# SCH_New-Project_2024-05-19.net
KiCad netlist of a schematic drawn in EasyEDA
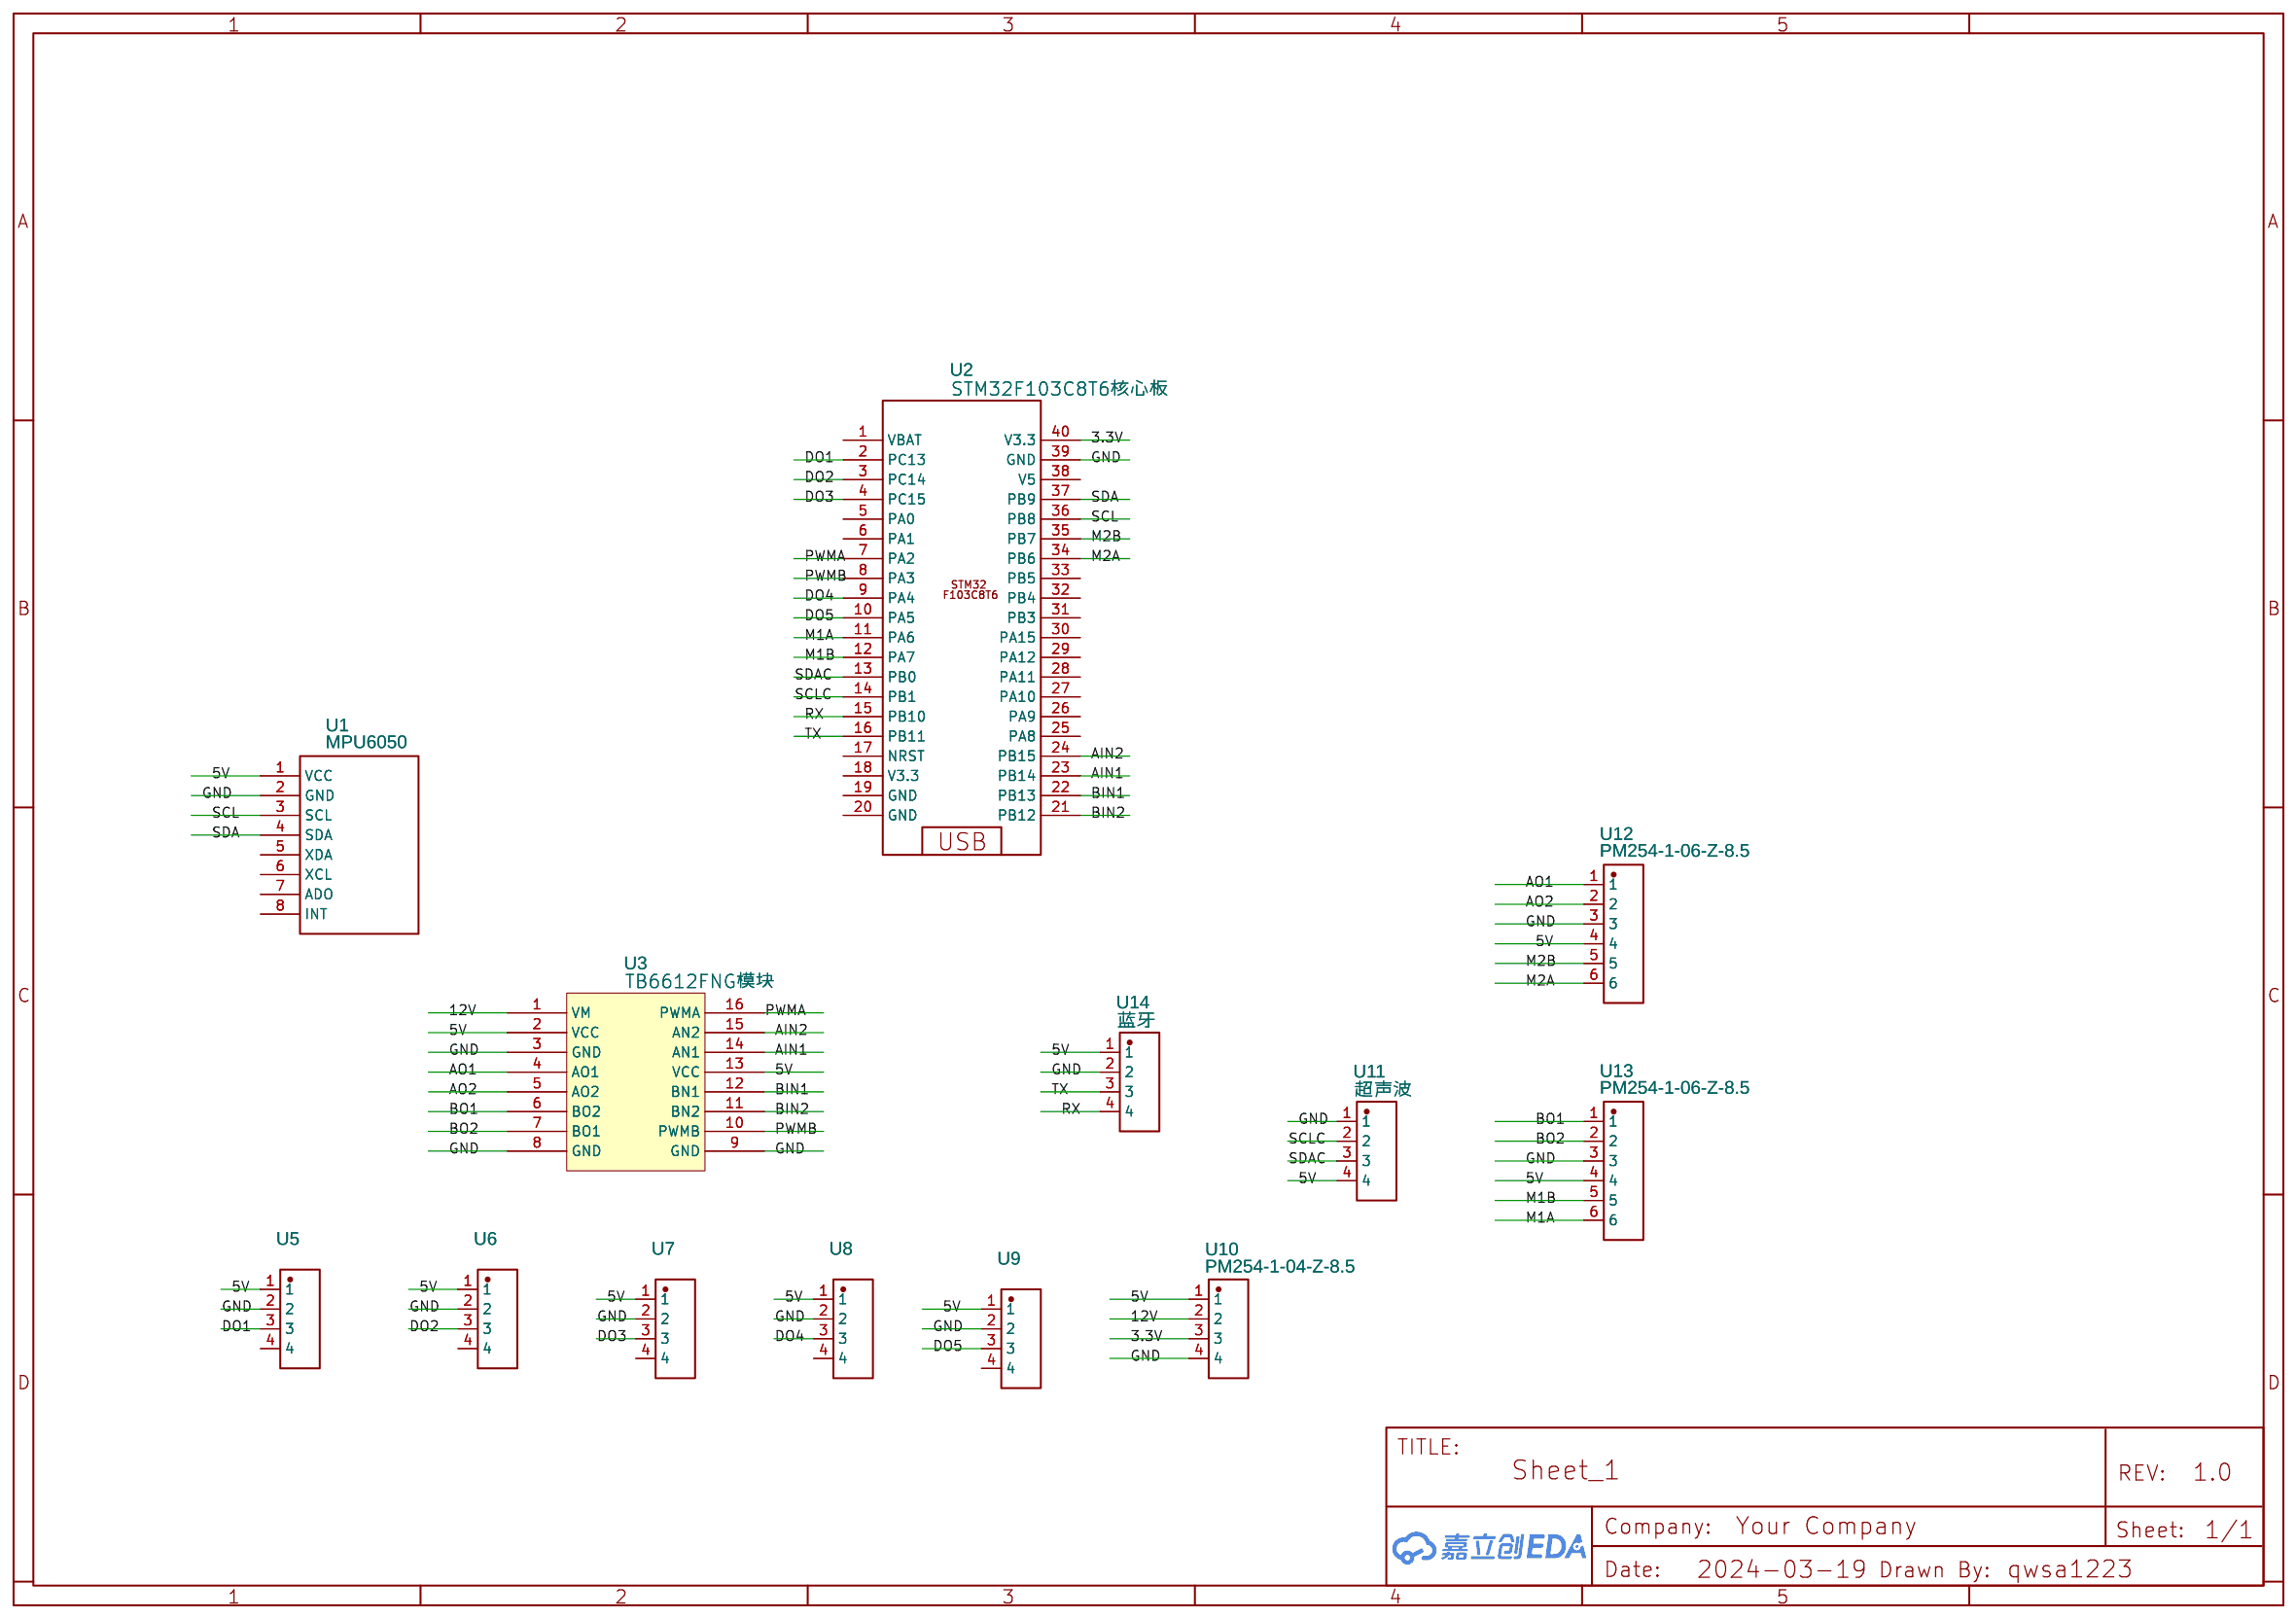
[diagram p0: schematic sheet]

(export (version "E")
  (design (tool "Eeschema 10.0.6"))
  (components
    (comp (ref "U1") (value "MPU6050") (libsource (lib "") (part "MPU6050")))
    (comp (ref "U2") (value "STM32F103C8T6核心板") (libsource (lib "") (part "STM32F103C8T6核心板")))
    (comp (ref "U3") (value "TB6612FNG模块") (libsource (lib "") (part "TB6612FNG模块")))
    (comp (ref "U5")
      (value "PM254-1-04-W-8.5")
      (fields (field (name "Manufacturer") "HCTL(华灿天禄)"))
      (libsource (lib "") (part "PM254-1-04-W-8.5"))
    )
    (comp (ref "U6")
      (value "PM254-1-04-W-8.5")
      (fields (field (name "Manufacturer") "HCTL(华灿天禄)"))
      (libsource (lib "") (part "PM254-1-04-W-8.5"))
    )
    (comp (ref "U7")
      (value "PM254-1-04-W-8.5")
      (fields (field (name "Manufacturer") "HCTL(华灿天禄)"))
      (libsource (lib "") (part "PM254-1-04-W-8.5"))
    )
    (comp (ref "U8")
      (value "PM254-1-04-W-8.5")
      (fields (field (name "Manufacturer") "HCTL(华灿天禄)"))
      (libsource (lib "") (part "PM254-1-04-W-8.5"))
    )
    (comp (ref "U9")
      (value "PM254-1-04-W-8.5")
      (fields (field (name "Manufacturer") "HCTL(华灿天禄)"))
      (libsource (lib "") (part "PM254-1-04-W-8.5"))
    )
    (comp (ref "U10")
      (value "PM254-1-04-Z-8.5")
      (fields (field (name "Manufacturer") "HCTL(华灿天禄)"))
      (libsource (lib "") (part "PM254-1-04-Z-8.5"))
    )
    (comp (ref "U11")
      (value "超声波")
      (fields
        (field (name "Manufacturer Part") "PM254-1-04-Z-8.5")
        (field (name "Manufacturer") "HCTL(华灿天禄)")
      )
      (libsource (lib "") (part "PM254-1-04-Z-8.5"))
    )
    (comp (ref "U12")
      (value "PM254-1-06-Z-8.5")
      (fields (field (name "Manufacturer") "HCTL(华灿天禄)"))
      (libsource (lib "") (part "PM254-1-06-Z-8.5"))
    )
    (comp (ref "U13")
      (value "PM254-1-06-Z-8.5")
      (fields (field (name "Manufacturer") "HCTL(华灿天禄)"))
      (libsource (lib "") (part "PM254-1-06-Z-8.5"))
    )
    (comp (ref "U14")
      (value "蓝牙")
      (fields
        (field (name "Manufacturer Part") "PM254-1-04-Z-8.5")
        (field (name "Manufacturer") "HCTL(华灿天禄)")
      )
      (libsource (lib "") (part "PM254-1-04-Z-8.5"))
    )
  )
  (nets
    (net (code "1") (name "/3.3V") (class "Default")
      (node (ref "U10") (pin "3") (pinfunction "3_3") (pintype "unspecified"))
      (node (ref "U2") (pin "40") (pinfunction "V3.3_40") (pintype "passive"))
    )
    (net (code "2") (name "/5V") (class "Default")
      (node (ref "U1") (pin "1") (pinfunction "VCC_1") (pintype "unspecified"))
      (node (ref "U10") (pin "1") (pinfunction "1_1") (pintype "unspecified"))
      (node (ref "U11") (pin "4") (pinfunction "4_4") (pintype "unspecified"))
      (node (ref "U12") (pin "4") (pinfunction "4_4") (pintype "unspecified"))
      (node (ref "U13") (pin "4") (pinfunction "4_4") (pintype "unspecified"))
      (node (ref "U14") (pin "1") (pinfunction "1_1") (pintype "unspecified"))
      (node (ref "U3") (pin "13") (pinfunction "VCC_13") (pintype "unspecified"))
      (node (ref "U3") (pin "2") (pinfunction "VCC_2") (pintype "unspecified"))
      (node (ref "U5") (pin "1") (pinfunction "1_1") (pintype "unspecified"))
      (node (ref "U6") (pin "1") (pinfunction "1_1") (pintype "unspecified"))
      (node (ref "U7") (pin "1") (pinfunction "1_1") (pintype "unspecified"))
      (node (ref "U8") (pin "1") (pinfunction "1_1") (pintype "unspecified"))
      (node (ref "U9") (pin "1") (pinfunction "1_1") (pintype "unspecified"))
    )
    (net (code "3") (name "/12V") (class "Default")
      (node (ref "U10") (pin "2") (pinfunction "2_2") (pintype "unspecified"))
      (node (ref "U3") (pin "1") (pinfunction "VM_1") (pintype "unspecified"))
    )
    (net (code "4") (name "/AIN1") (class "Default")
      (node (ref "U2") (pin "23") (pinfunction "PB14_23") (pintype "bidirectional"))
      (node (ref "U3") (pin "14") (pinfunction "AN1_14") (pintype "unspecified"))
    )
    (net (code "5") (name "/AIN2") (class "Default")
      (node (ref "U2") (pin "24") (pinfunction "PB15_24") (pintype "bidirectional"))
      (node (ref "U3") (pin "15") (pinfunction "AN2_15") (pintype "unspecified"))
    )
    (net (code "6") (name "/AO1") (class "Default")
      (node (ref "U12") (pin "1") (pinfunction "1_1") (pintype "unspecified"))
      (node (ref "U3") (pin "4") (pinfunction "AO1_4") (pintype "unspecified"))
    )
    (net (code "7") (name "/AO2") (class "Default")
      (node (ref "U12") (pin "2") (pinfunction "2_2") (pintype "unspecified"))
      (node (ref "U3") (pin "5") (pinfunction "AO2_5") (pintype "unspecified"))
    )
    (net (code "8") (name "/BIN1") (class "Default")
      (node (ref "U2") (pin "22") (pinfunction "PB13_22") (pintype "bidirectional"))
      (node (ref "U3") (pin "12") (pinfunction "BN1_12") (pintype "unspecified"))
    )
    (net (code "9") (name "/BIN2") (class "Default")
      (node (ref "U2") (pin "21") (pinfunction "PB12_21") (pintype "bidirectional"))
      (node (ref "U3") (pin "11") (pinfunction "BN2_11") (pintype "unspecified"))
    )
    (net (code "10") (name "/BO1") (class "Default")
      (node (ref "U13") (pin "1") (pinfunction "1_1") (pintype "unspecified"))
      (node (ref "U3") (pin "6") (pinfunction "BO2_6") (pintype "unspecified"))
    )
    (net (code "11") (name "/BO2") (class "Default")
      (node (ref "U13") (pin "2") (pinfunction "2_2") (pintype "unspecified"))
      (node (ref "U3") (pin "7") (pinfunction "BO1_7") (pintype "unspecified"))
    )
    (net (code "12") (name "/DO1") (class "Default")
      (node (ref "U2") (pin "2") (pinfunction "PC13_2") (pintype "bidirectional"))
      (node (ref "U5") (pin "3") (pinfunction "3_3") (pintype "unspecified"))
    )
    (net (code "13") (name "/DO2") (class "Default")
      (node (ref "U2") (pin "3") (pinfunction "PC14_3") (pintype "bidirectional"))
      (node (ref "U6") (pin "3") (pinfunction "3_3") (pintype "unspecified"))
    )
    (net (code "14") (name "/DO3") (class "Default")
      (node (ref "U2") (pin "4") (pinfunction "PC15_4") (pintype "bidirectional"))
      (node (ref "U7") (pin "3") (pinfunction "3_3") (pintype "unspecified"))
    )
    (net (code "15") (name "/DO4") (class "Default")
      (node (ref "U2") (pin "9") (pinfunction "PA4_9") (pintype "bidirectional"))
      (node (ref "U8") (pin "3") (pinfunction "3_3") (pintype "unspecified"))
    )
    (net (code "16") (name "/DO5") (class "Default")
      (node (ref "U2") (pin "10") (pinfunction "PA5_10") (pintype "bidirectional"))
      (node (ref "U9") (pin "3") (pinfunction "3_3") (pintype "unspecified"))
    )
    (net (code "17") (name "/GND") (class "Default")
      (node (ref "U1") (pin "2") (pinfunction "GND_2") (pintype "unspecified"))
      (node (ref "U10") (pin "4") (pinfunction "4_4") (pintype "unspecified"))
      (node (ref "U11") (pin "1") (pinfunction "1_1") (pintype "unspecified"))
      (node (ref "U12") (pin "3") (pinfunction "3_3") (pintype "unspecified"))
      (node (ref "U13") (pin "3") (pinfunction "3_3") (pintype "unspecified"))
      (node (ref "U14") (pin "2") (pinfunction "2_2") (pintype "unspecified"))
      (node (ref "U2") (pin "39") (pinfunction "GND_39") (pintype "passive"))
      (node (ref "U3") (pin "3") (pinfunction "GND_3") (pintype "unspecified"))
      (node (ref "U3") (pin "8") (pinfunction "GND_8") (pintype "unspecified"))
      (node (ref "U3") (pin "9") (pinfunction "GND_9") (pintype "unspecified"))
      (node (ref "U5") (pin "2") (pinfunction "2_2") (pintype "unspecified"))
      (node (ref "U6") (pin "2") (pinfunction "2_2") (pintype "unspecified"))
      (node (ref "U7") (pin "2") (pinfunction "2_2") (pintype "unspecified"))
      (node (ref "U8") (pin "2") (pinfunction "2_2") (pintype "unspecified"))
      (node (ref "U9") (pin "2") (pinfunction "2_2") (pintype "unspecified"))
    )
    (net (code "18") (name "/M1A") (class "Default")
      (node (ref "U13") (pin "6") (pinfunction "6_6") (pintype "unspecified"))
      (node (ref "U2") (pin "11") (pinfunction "PA6_11") (pintype "bidirectional"))
    )
    (net (code "19") (name "/M1B") (class "Default")
      (node (ref "U13") (pin "5") (pinfunction "5_5") (pintype "unspecified"))
      (node (ref "U2") (pin "12") (pinfunction "PA7_12") (pintype "bidirectional"))
    )
    (net (code "20") (name "/M2A") (class "Default")
      (node (ref "U12") (pin "6") (pinfunction "6_6") (pintype "unspecified"))
      (node (ref "U2") (pin "34") (pinfunction "PB6_34") (pintype "bidirectional"))
    )
    (net (code "21") (name "/M2B") (class "Default")
      (node (ref "U12") (pin "5") (pinfunction "5_5") (pintype "unspecified"))
      (node (ref "U2") (pin "35") (pinfunction "PB7_35") (pintype "bidirectional"))
    )
    (net (code "22") (name "/PWMA") (class "Default")
      (node (ref "U2") (pin "7") (pinfunction "PA2_7") (pintype "bidirectional"))
      (node (ref "U3") (pin "16") (pinfunction "PWMA_16") (pintype "unspecified"))
    )
    (net (code "23") (name "/PWMB") (class "Default")
      (node (ref "U2") (pin "8") (pinfunction "PA3_8") (pintype "bidirectional"))
      (node (ref "U3") (pin "10") (pinfunction "PWMB_10") (pintype "unspecified"))
    )
    (net (code "24") (name "/RX") (class "Default")
      (node (ref "U14") (pin "4") (pinfunction "4_4") (pintype "unspecified"))
      (node (ref "U2") (pin "15") (pinfunction "PB10_15") (pintype "bidirectional"))
    )
    (net (code "25") (name "/SCL") (class "Default")
      (node (ref "U1") (pin "3") (pinfunction "SCL_3") (pintype "unspecified"))
      (node (ref "U2") (pin "36") (pinfunction "PB8_36") (pintype "bidirectional"))
    )
    (net (code "26") (name "/SCLC") (class "Default")
      (node (ref "U11") (pin "2") (pinfunction "2_2") (pintype "unspecified"))
      (node (ref "U2") (pin "14") (pinfunction "PB1_14") (pintype "bidirectional"))
    )
    (net (code "27") (name "/SDA") (class "Default")
      (node (ref "U1") (pin "4") (pinfunction "SDA_4") (pintype "unspecified"))
      (node (ref "U2") (pin "37") (pinfunction "PB9_37") (pintype "bidirectional"))
    )
    (net (code "28") (name "/SDAC") (class "Default")
      (node (ref "U11") (pin "3") (pinfunction "3_3") (pintype "unspecified"))
      (node (ref "U2") (pin "13") (pinfunction "PB0_13") (pintype "bidirectional"))
    )
    (net (code "29") (name "/TX") (class "Default")
      (node (ref "U14") (pin "3") (pinfunction "3_3") (pintype "unspecified"))
      (node (ref "U2") (pin "16") (pinfunction "PB11_16") (pintype "bidirectional"))
    )
    (net (code "30") (name "unconnected-(U1-ADO-Pad7)") (class "Default")
      (node (ref "U1") (pin "7") (pinfunction "ADO_7") (pintype "unspecified"))
    )
    (net (code "31") (name "unconnected-(U1-INT-Pad8)") (class "Default")
      (node (ref "U1") (pin "8") (pinfunction "INT_8") (pintype "unspecified"))
    )
    (net (code "32") (name "unconnected-(U1-XCL-Pad6)") (class "Default")
      (node (ref "U1") (pin "6") (pinfunction "XCL_6") (pintype "unspecified"))
    )
    (net (code "33") (name "unconnected-(U1-XDA-Pad5)") (class "Default")
      (node (ref "U1") (pin "5") (pinfunction "XDA_5") (pintype "unspecified"))
    )
    (net (code "34") (name "unconnected-(U2-GND-Pad19)") (class "Default")
      (node (ref "U2") (pin "19") (pinfunction "GND_19") (pintype "passive"))
    )
    (net (code "35") (name "unconnected-(U2-GND-Pad20)") (class "Default")
      (node (ref "U2") (pin "20") (pinfunction "GND_20") (pintype "passive"))
    )
    (net (code "36") (name "unconnected-(U2-NRST-Pad17)") (class "Default")
      (node (ref "U2") (pin "17") (pinfunction "NRST_17") (pintype "bidirectional"))
    )
    (net (code "37") (name "unconnected-(U2-PA0-Pad5)") (class "Default")
      (node (ref "U2") (pin "5") (pinfunction "PA0_5") (pintype "bidirectional"))
    )
    (net (code "38") (name "unconnected-(U2-PA1-Pad6)") (class "Default")
      (node (ref "U2") (pin "6") (pinfunction "PA1_6") (pintype "bidirectional"))
    )
    (net (code "39") (name "unconnected-(U2-PA8-Pad25)") (class "Default")
      (node (ref "U2") (pin "25") (pinfunction "PA8_25") (pintype "bidirectional"))
    )
    (net (code "40") (name "unconnected-(U2-PA9-Pad26)") (class "Default")
      (node (ref "U2") (pin "26") (pinfunction "PA9_26") (pintype "bidirectional"))
    )
    (net (code "41") (name "unconnected-(U2-PA10-Pad27)") (class "Default")
      (node (ref "U2") (pin "27") (pinfunction "PA10_27") (pintype "bidirectional"))
    )
    (net (code "42") (name "unconnected-(U2-PA11-Pad28)") (class "Default")
      (node (ref "U2") (pin "28") (pinfunction "PA11_28") (pintype "bidirectional"))
    )
    (net (code "43") (name "unconnected-(U2-PA12-Pad29)") (class "Default")
      (node (ref "U2") (pin "29") (pinfunction "PA12_29") (pintype "bidirectional"))
    )
    (net (code "44") (name "unconnected-(U2-PA15-Pad30)") (class "Default")
      (node (ref "U2") (pin "30") (pinfunction "PA15_30") (pintype "bidirectional"))
    )
    (net (code "45") (name "unconnected-(U2-PB3-Pad31)") (class "Default")
      (node (ref "U2") (pin "31") (pinfunction "PB3_31") (pintype "bidirectional"))
    )
    (net (code "46") (name "unconnected-(U2-PB4-Pad32)") (class "Default")
      (node (ref "U2") (pin "32") (pinfunction "PB4_32") (pintype "bidirectional"))
    )
    (net (code "47") (name "unconnected-(U2-PB5-Pad33)") (class "Default")
      (node (ref "U2") (pin "33") (pinfunction "PB5_33") (pintype "bidirectional"))
    )
    (net (code "48") (name "unconnected-(U2-V3.3-Pad18)") (class "Default")
      (node (ref "U2") (pin "18") (pinfunction "V3.3_18") (pintype "passive"))
    )
    (net (code "49") (name "unconnected-(U2-V5-Pad38)") (class "Default")
      (node (ref "U2") (pin "38") (pinfunction "V5_38") (pintype "passive"))
    )
    (net (code "50") (name "unconnected-(U2-VBAT-Pad1)") (class "Default")
      (node (ref "U2") (pin "1") (pinfunction "VBAT_1") (pintype "passive"))
    )
    (net (code "51") (name "unconnected-(U5-Pad4)") (class "Default")
      (node (ref "U5") (pin "4") (pinfunction "4_4") (pintype "unspecified"))
    )
    (net (code "52") (name "unconnected-(U6-Pad4)") (class "Default")
      (node (ref "U6") (pin "4") (pinfunction "4_4") (pintype "unspecified"))
    )
    (net (code "53") (name "unconnected-(U7-Pad4)") (class "Default")
      (node (ref "U7") (pin "4") (pinfunction "4_4") (pintype "unspecified"))
    )
    (net (code "54") (name "unconnected-(U8-Pad4)") (class "Default")
      (node (ref "U8") (pin "4") (pinfunction "4_4") (pintype "unspecified"))
    )
    (net (code "55") (name "unconnected-(U9-Pad4)") (class "Default")
      (node (ref "U9") (pin "4") (pinfunction "4_4") (pintype "unspecified"))
    )
  )
)
